# Converter_3V3-VADJ.net
KiCad netlist of a schematic drawn in Altium Designer
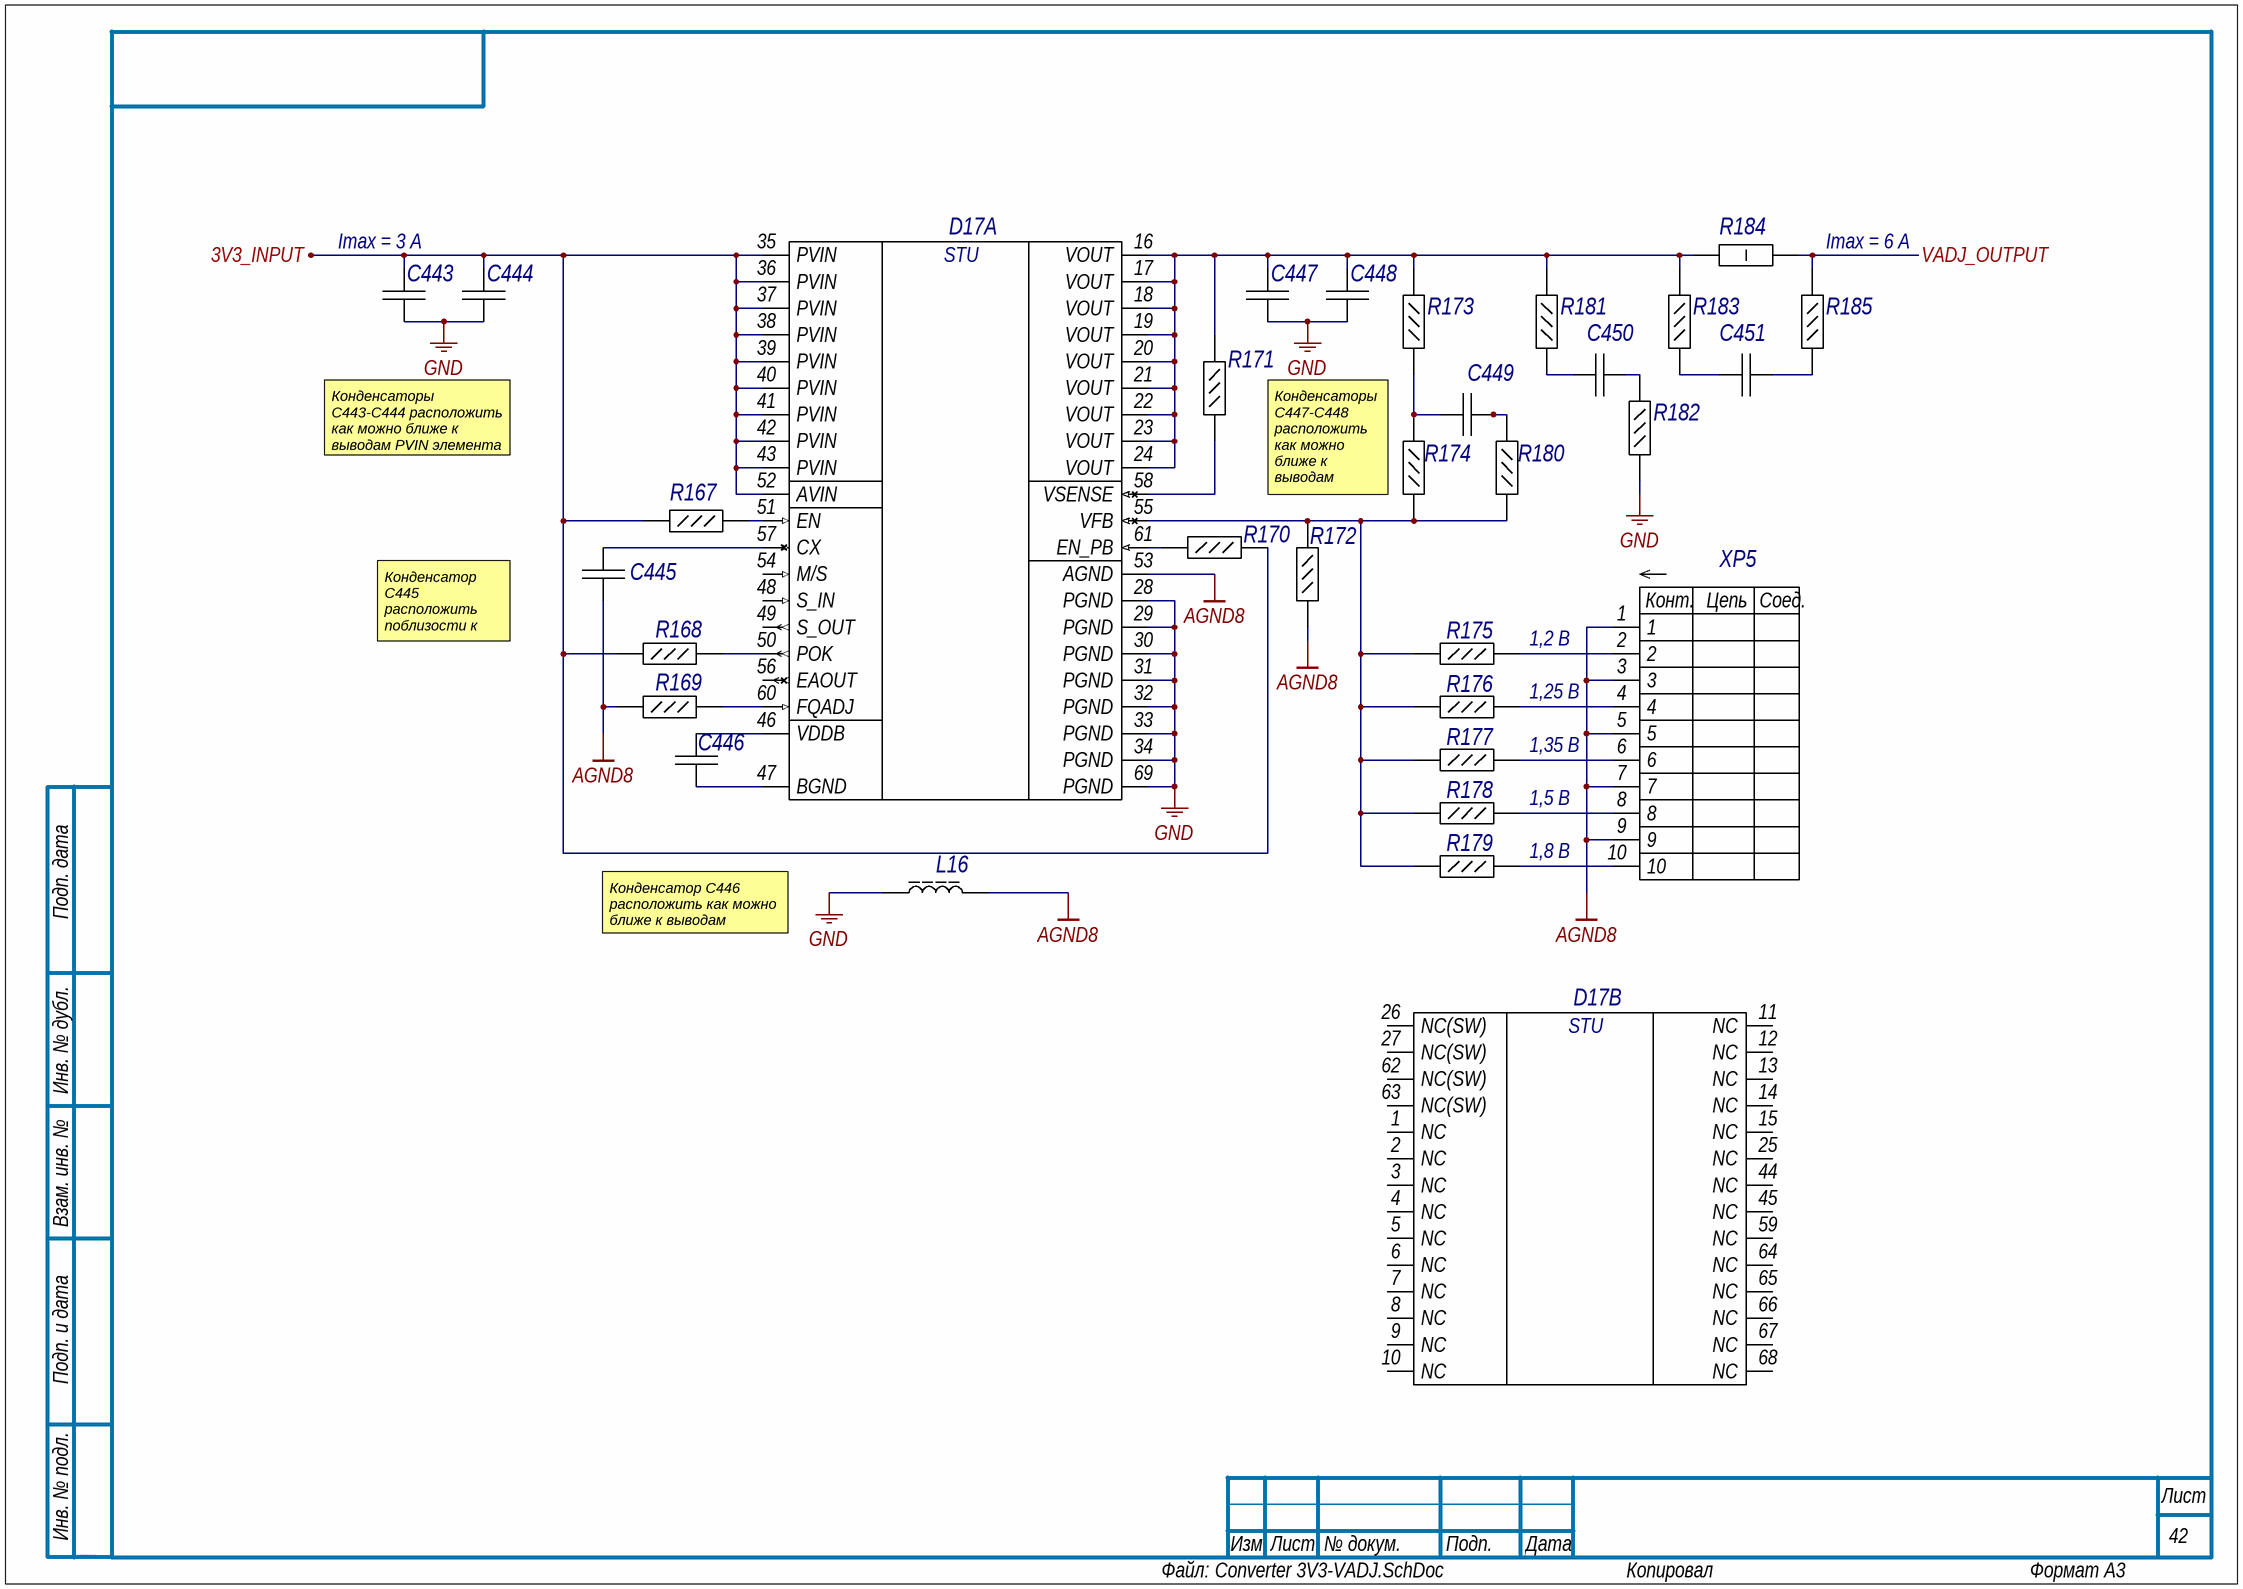
[diagram p0: Converter 3V3-VADJ.SchDoc]

(export (version "E")
  (design (tool "Eeschema 10.0.6"))
  (components
    (comp (ref "C443")
      (value "GRM31CR61E226KE15L")
      (footprint "CAPC3216X180X55ML20T25")
      (description "Chip Capacitor, 22 uF, +/- 10%, 25 V, -55 to 85 degC, 1206 (3216 Metric), RoHS, Tape and Reel")
      (fields (field (name "TOLERANCE") "10%"))
      (libsource (lib "MiniPC DB") (part "CAP_NP"))
    )
    (comp (ref "C444")
      (value "GRM31CR61E226KE15L")
      (footprint "CAPC3216X180X55ML20T25")
      (description "Chip Capacitor, 22 uF, +/- 10%, 25 V, -55 to 85 degC, 1206 (3216 Metric), RoHS, Tape and Reel")
      (fields (field (name "TOLERANCE") "10%"))
      (libsource (lib "MiniPC DB") (part "CAP_NP"))
    )
    (comp (ref "C445")
      (value "VJ0402Y153JXQPW1BC")
      (footprint "CAPC1005X55X23ML05T8")
      (description "Chip Capacitor, 15 nF, +/- 5%, 10 V, -55 to 125 degC, 0402 (1005 Metric), RoHS, Tape and Reel")
      (fields (field (name "TOLERANCE") "5%"))
      (libsource (lib "MiniPC DB") (part "CAP_NP"))
    )
    (comp (ref "C446")
      (value "GRM155R61A224KE19D")
      (footprint "CAPC1005X55X25NL05T10")
      (description "Chip Capacitor, 220 nF, +/- 10%, 10 V, -55 to 85 degC, 0402 (1005 Metric), RoHS, Tape and Reel")
      (fields (field (name "TOLERANCE") "10%") (field (name "MANUFACTURER") "Basic Passives"))
      (libsource (lib "MiniPC DB") (part "CAP_NP"))
    )
    (comp (ref "C447")
      (value "C3216X5R1A476M160AB")
      (footprint "CAPC3216X180X20ML20")
      (description "Chip Capacitor, 47 uF, +/- 20%, 10 V, -55 to 85 degC, 1206 (3216 Metric), RoHS, Tape and Reel")
      (fields (field (name "TOLERANCE") "20%"))
      (libsource (lib "MiniPC DB") (part "CAP_NP"))
    )
    (comp (ref "C448")
      (value "C3216X5R1A476M160AB")
      (footprint "CAPC3216X180X20ML20")
      (description "Chip Capacitor, 47 uF, +/- 20%, 10 V, -55 to 85 degC, 1206 (3216 Metric), RoHS, Tape and Reel")
      (fields (field (name "TOLERANCE") "20%"))
      (libsource (lib "MiniPC DB") (part "CAP_NP"))
    )
    (comp (ref "C449")
      (value "C1005C0G1H220J050BA")
      (footprint "CAPC1005X55X10LL05")
      (description "Chip Capacitor, 22 pF, +/- 5%, 50 V, -55 to 125 degC, 0402 (1005 Metric), RoHS, Tape and Reel")
      (fields (field (name "TOLERANCE") "5%"))
      (libsource (lib "MiniPC DB") (part "CAP_NP"))
    )
    (comp (ref "C450")
      (value "GRM155R61A224KE19D")
      (footprint "CAPC1005X55X25NL05T10")
      (description "Chip Capacitor, 220 nF, +/- 10%, 10 V, -55 to 85 degC, 0402 (1005 Metric), RoHS, Tape and Reel")
      (fields (field (name "TOLERANCE") "10%") (field (name "MANUFACTURER") "Basic Passives"))
      (libsource (lib "MiniPC DB") (part "CAP_NP"))
    )
    (comp (ref "C451")
      (value "CGB2A1X5R1E105K033BC")
      (footprint "CAPC1005X33X10LL5")
      (description "Chip Capacitor, 1 uF, +/- 10%, 25 V, -55 to 85 degC, 0402 (1005 Metric), RoHS, Tape and Reel")
      (fields (field (name "TOLERANCE") "10%"))
      (libsource (lib "MiniPC DB") (part "CAP_NP"))
    )
    (comp (ref "D17")
      (value "EN6360QI")
      (footprint "ALTR-QFN-68_A-305_V")
      (libsource (lib "MiniPC DB") (part "EN6360QI"))
    )
    (comp (ref "L16")
      (value "742792609")
      (footprint "SMD-0603")
      (description "SMD EMI Suppression Ferrite Bead WE-CBF, Z = 30 Ohm")
      (libsource (lib "MiniPC DB") (part "Choke"))
    )
    (comp (ref "R167")
      (value "ERJ-2GE0R00X")
      (footprint "RESC1005X40X25LL05T05")
      (description "Chip Resistor, 0 mOhm, +/- 5%, 100 mW, -55 to 155 degC, 0402 (1005 Metric), RoHS, Tape and Reel")
      (fields (field (name "TOLERANCE") "5%") (field (name "MANUFACTURER") "Basic Passives"))
      (libsource (lib "") (part "RES-0.05_1"))
    )
    (comp (ref "R168")
      (value "ERJ-2RKF1003X")
      (footprint "RESC1005X40X25LL05T05")
      (description "Chip Resistor, 100 KOhm, +/- 1%, 100 mW, -55 to 155 degC, 0402 (1005 Metric), RoHS, Tape and Reel")
      (fields (field (name "TOLERANCE") "1%") (field (name "MANUFACTURER") "Basic Passives"))
      (libsource (lib "") (part "RES-0.05_1"))
    )
    (comp (ref "R169")
      (value "ERJ-2RKF5491X")
      (footprint "RESC1005X40X25LL05T05")
      (description "Chip Resistor, 5.49 KOhm, +/- 1%, 100 mW, -55 to 155 degC, 0402 (1005 Metric), RoHS, Tape and Reel")
      (fields (field (name "TOLERANCE") "1%") (field (name "MANUFACTURER") "Basic Passives"))
      (libsource (lib "") (part "RES-0.05_1"))
    )
    (comp (ref "R170")
      (value "ERJ-2RKF1002X")
      (footprint "RESC1005X40X25LL05T05")
      (description "Chip Resistor, 10 KOhm, +/- 1%, 100 mW, -55 to 155 degC, 0402 (1005 Metric), RoHS, Tape and Reel")
      (fields (field (name "TOLERANCE") "1%") (field (name "MANUFACTURER") "Basic Passives"))
      (libsource (lib "") (part "RES-0.05_1"))
    )
    (comp (ref "R171")
      (value "ERJ-2GE0R00X")
      (footprint "RESC1005X40X25LL05T05")
      (description "Chip Resistor, 0 mOhm, +/- 5%, 100 mW, -55 to 155 degC, 0402 (1005 Metric), RoHS, Tape and Reel")
      (fields (field (name "TOLERANCE") "5%") (field (name "MANUFACTURER") "Basic Passives"))
      (libsource (lib "") (part "RES-0.05_2"))
    )
    (comp (ref "R172")
      (value "CRCW0402191KFKED")
      (footprint "RESC1005X40X25LL05T05")
      (description "Chip Resistor, 191 KOhm, +/- 1%, 63 mW, -55 to 155 degC, 0402 (1005 Metric), RoHS, Tape and Reel")
      (fields (field (name "TOLERANCE") "1%") (field (name "MANUFACTURER") "Basic Passives"))
      (libsource (lib "") (part "RES-0.05_2"))
    )
    (comp (ref "R173")
      (value "ERJ-2GE0R00X")
      (footprint "RESC1005X40X25LL05T05")
      (description "Chip Resistor, 0 mOhm, +/- 5%, 100 mW, -55 to 155 degC, 0402 (1005 Metric), RoHS, Tape and Reel")
      (fields (field (name "TOLERANCE") "5%") (field (name "MANUFACTURER") "Basic Passives"))
      (libsource (lib "MiniPC DB") (part "RES-0.05"))
    )
    (comp (ref "R174")
      (value "CRCW0402160KFKED")
      (footprint "RESC1005X40X25LL05T05")
      (description "Chip Resistor, 160 KOhm, +/- 1%, 63 mW, -55 to 155 degC, 0402 (1005 Metric), RoHS, Tape and Reel")
      (fields (field (name "TOLERANCE") "1%") (field (name "MANUFACTURER") "Basic Passives"))
      (libsource (lib "MiniPC DB") (part "RES-0.05"))
    )
    (comp (ref "R175")
      (value "CRCW0402976KFKED")
      (footprint "RESC1005X40X25LL05T05")
      (description "Chip Resistor, 976 KOhm, +/- 1%, 63 mW, -55 to 155 degC, 0402 (1005 Metric), RoHS, Tape and Reel")
      (fields (field (name "TOLERANCE") "1%") (field (name "MANUFACTURER") "Basic Passives"))
      (libsource (lib "") (part "RES-0.05_1"))
    )
    (comp (ref "R176")
      (value "CRCW0402649KFKED")
      (footprint "RESC1005X40X25LL05T05")
      (description "Chip Resistor, 649 KOhm, +/- 1%, 63 mW, -55 to 155 degC, 0402 (1005 Metric), RoHS, Tape and Reel")
      (fields (field (name "TOLERANCE") "1%") (field (name "MANUFACTURER") "Basic Passives"))
      (libsource (lib "") (part "RES-0.05_1"))
    )
    (comp (ref "R177")
      (value "CRCW0402390KFKED")
      (footprint "RESC1005X40X25LL05T05")
      (description "Chip Resistor, 390 KOhm, +/- 1%, 63 mW, -55 to 155 degC, 0402 (1005 Metric), RoHS, Tape and Reel")
      (fields (field (name "TOLERANCE") "1%") (field (name "MANUFACTURER") "Basic Passives"))
      (libsource (lib "") (part "RES-0.05_1"))
    )
    (comp (ref "R178")
      (value "ERJ-2RKF2403X")
      (footprint "RESC1005X40X25LL05T05")
      (description "Chip Resistor, 240 KOhm, +/- 1%, 100 mW, -55 to 155 degC, 0402 (1005 Metric), RoHS, Tape and Reel")
      (fields (field (name "TOLERANCE") "1%") (field (name "MANUFACTURER") "Basic Passives"))
      (libsource (lib "") (part "RES-0.05_1"))
    )
    (comp (ref "R179")
      (value "CRCW0402137KFKED")
      (footprint "RESC1005X40X25LL05T05")
      (description "Chip Resistor, 137 KOhm, +/- 1%, 63 mW, -55 to 155 degC, 0402 (1005 Metric), RoHS, Tape and Reel")
      (fields (field (name "TOLERANCE") "1%") (field (name "MANUFACTURER") "Basic Passives"))
      (libsource (lib "") (part "RES-0.05_1"))
    )
    (comp (ref "R180")
      (value "ERJ-2RKF1502X")
      (footprint "RESC1005X40X25LL05T05")
      (description "Chip Resistor, 15 KOhm, +/- 1%, 100 mW, -55 to 155 degC, 0402 (1005 Metric), RoHS, Tape and Reel")
      (fields (field (name "TOLERANCE") "1%") (field (name "MANUFACTURER") "Basic Passives"))
      (libsource (lib "MiniPC DB") (part "RES-0.05"))
    )
    (comp (ref "R181")
      (value "ERJ-2RKF1000X")
      (footprint "RESC1005X40X25LL05T05")
      (description "Chip Resistor, 100 Ohm, +/- 1%, 100 mW, -55 to 155 degC, 0402 (1005 Metric), RoHS, Tape and Reel")
      (fields (field (name "TOLERANCE") "1%") (field (name "MANUFACTURER") "Basic Passives"))
      (libsource (lib "MiniPC DB") (part "RES-0.05"))
    )
    (comp (ref "R182")
      (value "ERJ-2RKF1000X")
      (footprint "RESC1005X40X25LL05T05")
      (description "Chip Resistor, 100 Ohm, +/- 1%, 100 mW, -55 to 155 degC, 0402 (1005 Metric), RoHS, Tape and Reel")
      (fields (field (name "TOLERANCE") "1%") (field (name "MANUFACTURER") "Basic Passives"))
      (libsource (lib "") (part "RES-0.05_2"))
    )
    (comp (ref "R183")
      (value "ERJ-2RKF1002X")
      (footprint "RESC1005X40X25LL05T05")
      (description "Chip Resistor, 10 KOhm, +/- 1%, 100 mW, -55 to 155 degC, 0402 (1005 Metric), RoHS, Tape and Reel")
      (fields (field (name "TOLERANCE") "1%") (field (name "MANUFACTURER") "Basic Passives"))
      (libsource (lib "") (part "RES-0.05_2"))
    )
    (comp (ref "R184")
      (value "WSLP12061L000FEA")
      (footprint "RESC3216X89X104LL25T25")
      (description "Chip Resistor, 0.001 Ohm, +/- 1%, 1 W, -65 to 170 degC, 1206 (3216 Metric), RoHS, Tape and Reel")
      (fields (field (name "TOLERANCE") "1%"))
      (libsource (lib "MiniPC DB") (part "RES-1"))
    )
    (comp (ref "R185")
      (value "ERJ-2RKF1002X")
      (footprint "RESC1005X40X25LL05T05")
      (description "Chip Resistor, 10 KOhm, +/- 1%, 100 mW, -55 to 155 degC, 0402 (1005 Metric), RoHS, Tape and Reel")
      (fields (field (name "TOLERANCE") "1%") (field (name "MANUFACTURER") "Basic Passives"))
      (libsource (lib "") (part "RES-0.05_2"))
    )
    (comp (ref "XP5")
      (value "TSM-105-01-T-DV-TR")
      (footprint "SMTC-TSM-105-01-T-DV_V")
      (description "Male Header, Pitch 2.54 mm, 2 x 5 Position, Height 9.65 mm, -55 to 105 degC, RoHS, Tape and Reel")
      (libsource (lib "MiniPC DB") (part "VILKA_10K"))
    )
  )
  (nets
    (net (code "1") (name "/3V3_INPUT") (class "Default")
      (node (ref "C443") (pin "2") (pinfunction "2_2") (pintype "passive"))
      (node (ref "C444") (pin "2") (pinfunction "2_2") (pintype "passive"))
      (node (ref "D17") (pin "35") (pinfunction "PVIN_35") (pintype "power_in"))
      (node (ref "D17") (pin "36") (pinfunction "PVIN_36") (pintype "power_in"))
      (node (ref "D17") (pin "37") (pinfunction "PVIN_37") (pintype "power_in"))
      (node (ref "D17") (pin "38") (pinfunction "PVIN_38") (pintype "power_in"))
      (node (ref "D17") (pin "39") (pinfunction "PVIN_39") (pintype "power_in"))
      (node (ref "D17") (pin "40") (pinfunction "PVIN_40") (pintype "power_in"))
      (node (ref "D17") (pin "41") (pinfunction "PVIN_41") (pintype "power_in"))
      (node (ref "D17") (pin "42") (pinfunction "PVIN_42") (pintype "power_in"))
      (node (ref "D17") (pin "43") (pinfunction "PVIN_43") (pintype "power_in"))
      (node (ref "D17") (pin "52") (pinfunction "AVIN_52") (pintype "power_in"))
      (node (ref "R167") (pin "2") (pinfunction "2_2") (pintype "passive"))
      (node (ref "R168") (pin "2") (pinfunction "2_2") (pintype "passive"))
      (node (ref "R170") (pin "1") (pinfunction "1_1") (pintype "passive"))
    )
    (net (code "2") (name "/VADJ_OUTPUT") (class "Default")
      (node (ref "R184") (pin "1") (pinfunction "1_1") (pintype "passive"))
      (node (ref "R185") (pin "2") (pinfunction "2_2") (pintype "passive"))
    )
    (net (code "3") (name "AGND8") (class "Default")
      (node (ref "C445") (pin "1") (pinfunction "1_1") (pintype "passive"))
      (node (ref "D17") (pin "53") (pinfunction "AGND_53") (pintype "power_in"))
      (node (ref "L16") (pin "2") (pinfunction "2_2") (pintype "passive"))
      (node (ref "R169") (pin "2") (pinfunction "2_2") (pintype "passive"))
      (node (ref "R172") (pin "1") (pinfunction "1_1") (pintype "passive"))
      (node (ref "XP5") (pin "1") (pinfunction "1_1") (pintype "passive"))
      (node (ref "XP5") (pin "3") (pinfunction "3_3") (pintype "passive"))
      (node (ref "XP5") (pin "5") (pinfunction "5_5") (pintype "passive"))
      (node (ref "XP5") (pin "7") (pinfunction "7_7") (pintype "passive"))
      (node (ref "XP5") (pin "9") (pinfunction "9_9") (pintype "passive"))
    )
    (net (code "4") (name "GND") (class "Default")
      (node (ref "C443") (pin "1") (pinfunction "1_1") (pintype "passive"))
      (node (ref "C444") (pin "1") (pinfunction "1_1") (pintype "passive"))
      (node (ref "C447") (pin "1") (pinfunction "1_1") (pintype "passive"))
      (node (ref "C448") (pin "1") (pinfunction "1_1") (pintype "passive"))
      (node (ref "D17") (pin "28") (pinfunction "PGND_28") (pintype "power_in"))
      (node (ref "D17") (pin "29") (pinfunction "PGND_29") (pintype "power_in"))
      (node (ref "D17") (pin "30") (pinfunction "PGND_30") (pintype "power_in"))
      (node (ref "D17") (pin "31") (pinfunction "PGND_31") (pintype "power_in"))
      (node (ref "D17") (pin "32") (pinfunction "PGND_32") (pintype "power_in"))
      (node (ref "D17") (pin "33") (pinfunction "PGND_33") (pintype "power_in"))
      (node (ref "D17") (pin "34") (pinfunction "PGND_34") (pintype "power_in"))
      (node (ref "D17") (pin "69") (pinfunction "PGND_69") (pintype "power_in"))
      (node (ref "L16") (pin "1") (pinfunction "1_1") (pintype "passive"))
      (node (ref "R182") (pin "1") (pinfunction "1_1") (pintype "passive"))
    )
    (net (code "5") (name "Net-(C447-Pad2)") (class "Default")
      (node (ref "C447") (pin "2") (pinfunction "2_2") (pintype "passive"))
      (node (ref "C448") (pin "2") (pinfunction "2_2") (pintype "passive"))
      (node (ref "D17") (pin "16") (pinfunction "VOUT_16") (pintype "power_in"))
      (node (ref "D17") (pin "17") (pinfunction "VOUT_17") (pintype "power_in"))
      (node (ref "D17") (pin "18") (pinfunction "VOUT_18") (pintype "power_in"))
      (node (ref "D17") (pin "19") (pinfunction "VOUT_19") (pintype "power_in"))
      (node (ref "D17") (pin "20") (pinfunction "VOUT_20") (pintype "power_in"))
      (node (ref "D17") (pin "21") (pinfunction "VOUT_21") (pintype "power_in"))
      (node (ref "D17") (pin "22") (pinfunction "VOUT_22") (pintype "power_in"))
      (node (ref "D17") (pin "23") (pinfunction "VOUT_23") (pintype "power_in"))
      (node (ref "D17") (pin "24") (pinfunction "VOUT_24") (pintype "power_in"))
      (node (ref "R171") (pin "2") (pinfunction "2_2") (pintype "passive"))
      (node (ref "R173") (pin "1") (pinfunction "1_1") (pintype "passive"))
      (node (ref "R181") (pin "1") (pinfunction "1_1") (pintype "passive"))
      (node (ref "R183") (pin "2") (pinfunction "2_2") (pintype "passive"))
      (node (ref "R184") (pin "2") (pinfunction "2_2") (pintype "passive"))
    )
    (net (code "6") (name "Net-(C449-Pad1)") (class "Default")
      (node (ref "C449") (pin "1") (pinfunction "1_1") (pintype "passive"))
      (node (ref "R173") (pin "2") (pinfunction "2_2") (pintype "passive"))
      (node (ref "R174") (pin "1") (pinfunction "1_1") (pintype "passive"))
    )
    (net (code "7") (name "Net-(C449-Pad2)") (class "Default")
      (node (ref "C449") (pin "2") (pinfunction "2_2") (pintype "passive"))
      (node (ref "R180") (pin "1") (pinfunction "1_1") (pintype "passive"))
    )
    (net (code "8") (name "Net-(C450-Pad1)") (class "Default")
      (node (ref "C450") (pin "1") (pinfunction "1_1") (pintype "passive"))
      (node (ref "R181") (pin "2") (pinfunction "2_2") (pintype "passive"))
    )
    (net (code "9") (name "Net-(C450-Pad2)") (class "Default")
      (node (ref "C450") (pin "2") (pinfunction "2_2") (pintype "passive"))
      (node (ref "R182") (pin "2") (pinfunction "2_2") (pintype "passive"))
    )
    (net (code "10") (name "Net-(C451-Pad1)") (class "Default")
      (node (ref "C451") (pin "1") (pinfunction "1_1") (pintype "passive"))
      (node (ref "R185") (pin "1") (pinfunction "1_1") (pintype "passive"))
    )
    (net (code "11") (name "Net-(C451-Pad2)") (class "Default")
      (node (ref "C451") (pin "2") (pinfunction "2_2") (pintype "passive"))
      (node (ref "R183") (pin "1") (pinfunction "1_1") (pintype "passive"))
    )
    (net (code "12") (name "Net-(D17A-BGND)") (class "Default")
      (node (ref "C446") (pin "1") (pinfunction "1_1") (pintype "passive"))
      (node (ref "D17") (pin "47") (pinfunction "BGND_47") (pintype "power_in"))
    )
    (net (code "13") (name "Net-(D17A-CX)") (class "Default")
      (node (ref "C445") (pin "2") (pinfunction "2_2") (pintype "passive"))
      (node (ref "D17") (pin "57") (pinfunction "CX_57") (pintype "input"))
    )
    (net (code "14") (name "Net-(D17A-EN)") (class "Default")
      (node (ref "D17") (pin "51") (pinfunction "EN_51") (pintype "input"))
      (node (ref "R167") (pin "1") (pinfunction "1_1") (pintype "passive"))
    )
    (net (code "15") (name "Net-(D17A-EN_PB)") (class "Default")
      (node (ref "D17") (pin "61") (pinfunction "EN_PB_61") (pintype "input"))
      (node (ref "R170") (pin "2") (pinfunction "2_2") (pintype "passive"))
    )
    (net (code "16") (name "Net-(D17A-FQADJ)") (class "Default")
      (node (ref "D17") (pin "60") (pinfunction "FQADJ_60") (pintype "input"))
      (node (ref "R169") (pin "1") (pinfunction "1_1") (pintype "passive"))
    )
    (net (code "17") (name "Net-(D17A-POK)") (class "Default")
      (node (ref "D17") (pin "50") (pinfunction "POK_50") (pintype "output"))
      (node (ref "R168") (pin "1") (pinfunction "1_1") (pintype "passive"))
    )
    (net (code "18") (name "Net-(D17A-VDDB)") (class "Default")
      (node (ref "C446") (pin "2") (pinfunction "2_2") (pintype "passive"))
      (node (ref "D17") (pin "46") (pinfunction "VDDB_46") (pintype "power_in"))
    )
    (net (code "19") (name "Net-(D17A-VFB)") (class "Default")
      (node (ref "D17") (pin "55") (pinfunction "VFB_55") (pintype "input"))
      (node (ref "R172") (pin "2") (pinfunction "2_2") (pintype "passive"))
      (node (ref "R174") (pin "2") (pinfunction "2_2") (pintype "passive"))
      (node (ref "R175") (pin "2") (pinfunction "2_2") (pintype "passive"))
      (node (ref "R176") (pin "2") (pinfunction "2_2") (pintype "passive"))
      (node (ref "R177") (pin "2") (pinfunction "2_2") (pintype "passive"))
      (node (ref "R178") (pin "2") (pinfunction "2_2") (pintype "passive"))
      (node (ref "R179") (pin "2") (pinfunction "2_2") (pintype "passive"))
      (node (ref "R180") (pin "2") (pinfunction "2_2") (pintype "passive"))
    )
    (net (code "20") (name "Net-(D17A-VSENSE)") (class "Default")
      (node (ref "D17") (pin "58") (pinfunction "VSENSE_58") (pintype "input"))
      (node (ref "R171") (pin "1") (pinfunction "1_1") (pintype "passive"))
    )
    (net (code "21") (name "Net-(R175-Pad1)") (class "Default")
      (node (ref "R175") (pin "1") (pinfunction "1_1") (pintype "passive"))
      (node (ref "XP5") (pin "2") (pinfunction "2_2") (pintype "passive"))
    )
    (net (code "22") (name "Net-(R176-Pad1)") (class "Default")
      (node (ref "R176") (pin "1") (pinfunction "1_1") (pintype "passive"))
      (node (ref "XP5") (pin "4") (pinfunction "4_4") (pintype "passive"))
    )
    (net (code "23") (name "Net-(R177-Pad1)") (class "Default")
      (node (ref "R177") (pin "1") (pinfunction "1_1") (pintype "passive"))
      (node (ref "XP5") (pin "6") (pinfunction "6_6") (pintype "passive"))
    )
    (net (code "24") (name "Net-(R178-Pad1)") (class "Default")
      (node (ref "R178") (pin "1") (pinfunction "1_1") (pintype "passive"))
      (node (ref "XP5") (pin "8") (pinfunction "8_8") (pintype "passive"))
    )
    (net (code "25") (name "Net-(R179-Pad1)") (class "Default")
      (node (ref "R179") (pin "1") (pinfunction "1_1") (pintype "passive"))
      (node (ref "XP5") (pin "10") (pinfunction "10_10") (pintype "passive"))
    )
    (net (code "26") (name "unconnected-(D17A-EAOUT-Pad56)") (class "Default")
      (node (ref "D17") (pin "56") (pinfunction "EAOUT_56") (pintype "output"))
    )
    (net (code "27") (name "unconnected-(D17A-M{slash}S-Pad54)") (class "Default")
      (node (ref "D17") (pin "54") (pinfunction "M/S_54") (pintype "input"))
    )
    (net (code "28") (name "unconnected-(D17A-S_IN-Pad48)") (class "Default")
      (node (ref "D17") (pin "48") (pinfunction "S_IN_48") (pintype "input"))
    )
    (net (code "29") (name "unconnected-(D17A-S_OUT-Pad49)") (class "Default")
      (node (ref "D17") (pin "49") (pinfunction "S_OUT_49") (pintype "output"))
    )
    (net (code "30") (name "unconnected-(D17B-NC(SW)-Pad26)") (class "Default")
      (node (ref "D17") (pin "26") (pinfunction "NC(SW)_26") (pintype "passive"))
    )
    (net (code "31") (name "unconnected-(D17B-NC(SW)-Pad27)") (class "Default")
      (node (ref "D17") (pin "27") (pinfunction "NC(SW)_27") (pintype "passive"))
    )
    (net (code "32") (name "unconnected-(D17B-NC(SW)-Pad62)") (class "Default")
      (node (ref "D17") (pin "62") (pinfunction "NC(SW)_62") (pintype "passive"))
    )
    (net (code "33") (name "unconnected-(D17B-NC(SW)-Pad63)") (class "Default")
      (node (ref "D17") (pin "63") (pinfunction "NC(SW)_63") (pintype "passive"))
    )
    (net (code "34") (name "unconnected-(D17B-NC-Pad1)") (class "Default")
      (node (ref "D17") (pin "1") (pinfunction "NC_1") (pintype "passive"))
    )
    (net (code "35") (name "unconnected-(D17B-NC-Pad2)") (class "Default")
      (node (ref "D17") (pin "2") (pinfunction "NC_2") (pintype "passive"))
    )
    (net (code "36") (name "unconnected-(D17B-NC-Pad3)") (class "Default")
      (node (ref "D17") (pin "3") (pinfunction "NC_3") (pintype "passive"))
    )
    (net (code "37") (name "unconnected-(D17B-NC-Pad4)") (class "Default")
      (node (ref "D17") (pin "4") (pinfunction "NC_4") (pintype "passive"))
    )
    (net (code "38") (name "unconnected-(D17B-NC-Pad5)") (class "Default")
      (node (ref "D17") (pin "5") (pinfunction "NC_5") (pintype "passive"))
    )
    (net (code "39") (name "unconnected-(D17B-NC-Pad6)") (class "Default")
      (node (ref "D17") (pin "6") (pinfunction "NC_6") (pintype "passive"))
    )
    (net (code "40") (name "unconnected-(D17B-NC-Pad7)") (class "Default")
      (node (ref "D17") (pin "7") (pinfunction "NC_7") (pintype "passive"))
    )
    (net (code "41") (name "unconnected-(D17B-NC-Pad8)") (class "Default")
      (node (ref "D17") (pin "8") (pinfunction "NC_8") (pintype "passive"))
    )
    (net (code "42") (name "unconnected-(D17B-NC-Pad9)") (class "Default")
      (node (ref "D17") (pin "9") (pinfunction "NC_9") (pintype "passive"))
    )
    (net (code "43") (name "unconnected-(D17B-NC-Pad10)") (class "Default")
      (node (ref "D17") (pin "10") (pinfunction "NC_10") (pintype "passive"))
    )
    (net (code "44") (name "unconnected-(D17B-NC-Pad11)") (class "Default")
      (node (ref "D17") (pin "11") (pinfunction "NC_11") (pintype "passive"))
    )
    (net (code "45") (name "unconnected-(D17B-NC-Pad12)") (class "Default")
      (node (ref "D17") (pin "12") (pinfunction "NC_12") (pintype "passive"))
    )
    (net (code "46") (name "unconnected-(D17B-NC-Pad13)") (class "Default")
      (node (ref "D17") (pin "13") (pinfunction "NC_13") (pintype "passive"))
    )
    (net (code "47") (name "unconnected-(D17B-NC-Pad14)") (class "Default")
      (node (ref "D17") (pin "14") (pinfunction "NC_14") (pintype "passive"))
    )
    (net (code "48") (name "unconnected-(D17B-NC-Pad15)") (class "Default")
      (node (ref "D17") (pin "15") (pinfunction "NC_15") (pintype "passive"))
    )
    (net (code "49") (name "unconnected-(D17B-NC-Pad25)") (class "Default")
      (node (ref "D17") (pin "25") (pinfunction "NC_25") (pintype "passive"))
    )
    (net (code "50") (name "unconnected-(D17B-NC-Pad44)") (class "Default")
      (node (ref "D17") (pin "44") (pinfunction "NC_44") (pintype "passive"))
    )
    (net (code "51") (name "unconnected-(D17B-NC-Pad45)") (class "Default")
      (node (ref "D17") (pin "45") (pinfunction "NC_45") (pintype "passive"))
    )
    (net (code "52") (name "unconnected-(D17B-NC-Pad59)") (class "Default")
      (node (ref "D17") (pin "59") (pinfunction "NC_59") (pintype "passive"))
    )
    (net (code "53") (name "unconnected-(D17B-NC-Pad64)") (class "Default")
      (node (ref "D17") (pin "64") (pinfunction "NC_64") (pintype "passive"))
    )
    (net (code "54") (name "unconnected-(D17B-NC-Pad65)") (class "Default")
      (node (ref "D17") (pin "65") (pinfunction "NC_65") (pintype "passive"))
    )
    (net (code "55") (name "unconnected-(D17B-NC-Pad66)") (class "Default")
      (node (ref "D17") (pin "66") (pinfunction "NC_66") (pintype "passive"))
    )
    (net (code "56") (name "unconnected-(D17B-NC-Pad67)") (class "Default")
      (node (ref "D17") (pin "67") (pinfunction "NC_67") (pintype "passive"))
    )
    (net (code "57") (name "unconnected-(D17B-NC-Pad68)") (class "Default")
      (node (ref "D17") (pin "68") (pinfunction "NC_68") (pintype "passive"))
    )
  )
)
